# USB.net
KiCad netlist of a schematic drawn in Altium Designer
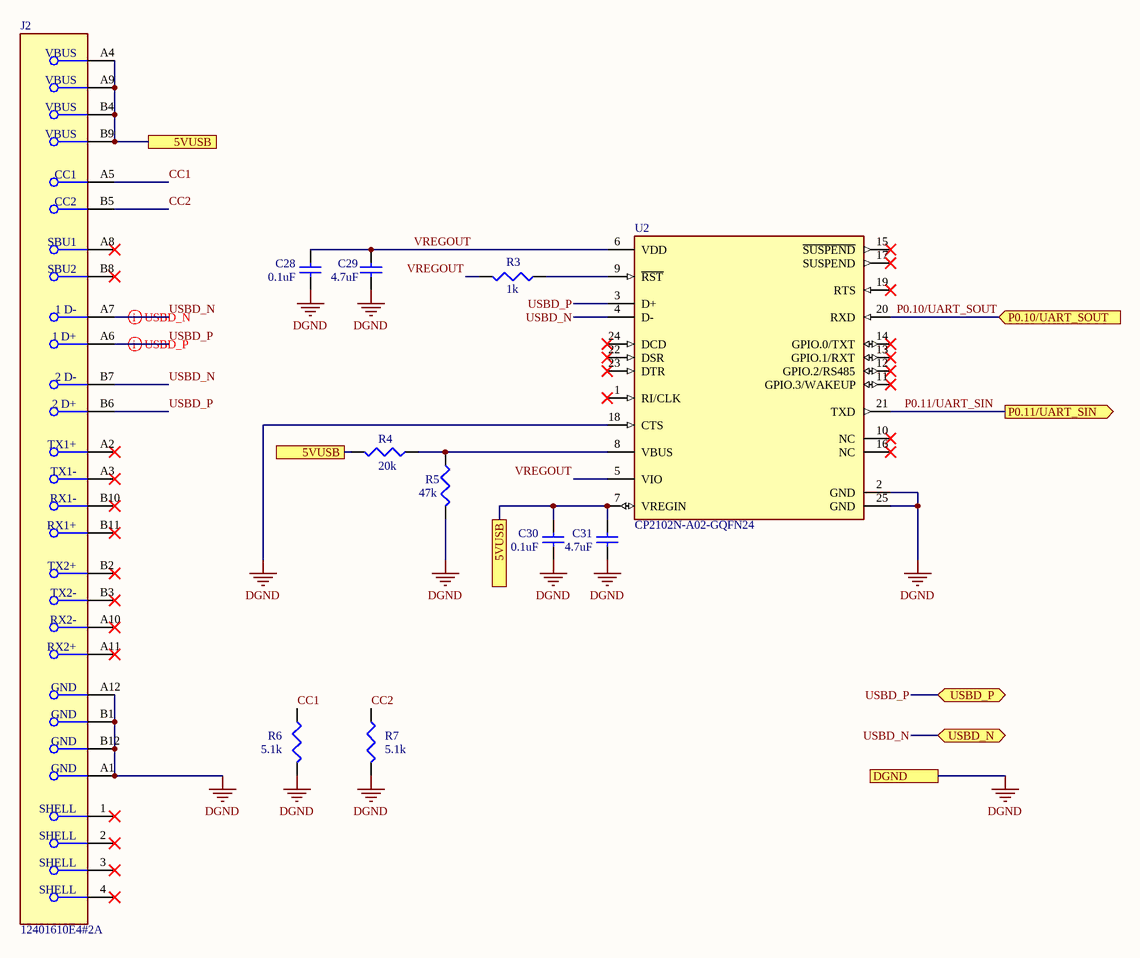
[diagram p0: USB.SchDoc]

(export (version "E")
  (design (tool "Eeschema 10.0.6"))
  (components
    (comp (ref "C28")
      (value "0.1uF")
      (footprint "0402 SMD")
      (description "0.1 µF ±10% 16V Ceramic Capacitor X7R 0402 (1005 Metric) Kemet")
      (fields (field (name "Comment") "C0402C104K4RAC7867"))
      (libsource (lib "ACEstat") (part "C0402C104K4RAC7867"))
    )
    (comp (ref "C29")
      (value "4.7uF")
      (footprint "0402 SMD")
      (description "4.7 µF ±10% 6.3V Ceramic Capacitor X5R 0402 (1005 Metric) Samsung")
      (fields (field (name "Comment") "CL05A475KQ5NRNC"))
      (libsource (lib "ACEstat") (part "CL05A475KQ5NRNC"))
    )
    (comp (ref "C30")
      (value "0.1uF")
      (footprint "0402 SMD")
      (description "0.1 µF ±10% 16V Ceramic Capacitor X7R 0402 (1005 Metric) Kemet")
      (fields (field (name "Comment") "C0402C104K4RAC7867"))
      (libsource (lib "ACEstat") (part "C0402C104K4RAC7867"))
    )
    (comp (ref "C31")
      (value "4.7uF")
      (footprint "0402 SMD")
      (description "4.7 µF ±10% 6.3V Ceramic Capacitor X5R 0402 (1005 Metric) Samsung")
      (fields (field (name "Comment") "CL05A475KQ5NRNC"))
      (libsource (lib "ACEstat") (part "CL05A475KQ5NRNC"))
    )
    (comp (ref "J2")
      (value "12401610E4#2A")
      (footprint "FP-12401610E4#2A-MFG")
      (description "CONN RCP USB3.1 TYPEC 24P SMD RA")
      (libsource (lib "Altium Content Vault") (part "7c76f4c47d7e2af8b8797da79635f2a"))
    )
    (comp (ref "R3")
      (value "1k")
      (footprint "0402 SMD")
      (description "1 kOhms ±1% 0.063W, 1/16W Chip Resistor 0402 (1005 Metric) Moisture Resistant Thick Film")
      (fields (field (name "Comment") "RC0402FR-071KL"))
      (libsource (lib "ACEstat") (part "RC0402FR-071KL"))
    )
    (comp (ref "R4")
      (value "20k")
      (footprint "0402 SMD")
      (description "20 kOhms ±1% 0.063W, 1/16W Chip Resistor 0402 (1005 Metric) Moisture Resistant Thick Film")
      (fields (field (name "Comment") "RC0402FR-0720KL"))
      (libsource (lib "ACEstat") (part "RC0402FR-0720KL"))
    )
    (comp (ref "R5")
      (value "47k")
      (footprint "0402 SMD")
      (description "47 kOhms ±1% 0.063W, 1/16W Chip Resistor 0402 (1005 Metric) Moisture Resistant Thick Film")
      (fields (field (name "Comment") "RC0402FR-0747KL"))
      (libsource (lib "ACEstat") (part "RC0402FR-0747KL"))
    )
    (comp (ref "R6")
      (value "5.1k")
      (footprint "0402 SMD")
      (description "5.1 kOhms ±1% 0.063W, 1/16W Chip Resistor 0402 (1005 Metric) Moisture Resistant Thick Film")
      (fields (field (name "Comment") "RC0402FR-075K1L"))
      (libsource (lib "ACEstat") (part "RC0402FR-075K1L"))
    )
    (comp (ref "R7")
      (value "5.1k")
      (footprint "0402 SMD")
      (description "5.1 kOhms ±1% 0.063W, 1/16W Chip Resistor 0402 (1005 Metric) Moisture Resistant Thick Film")
      (fields (field (name "Comment") "RC0402FR-075K1L"))
      (libsource (lib "ACEstat") (part "RC0402FR-075K1L"))
    )
    (comp (ref "U2")
      (value "CP2102N-A02-GQFN24")
      (footprint "FP-CP2102N-A02-GQFN24R-IPC_A")
      (description "IC USB TO UART BRIDGE QFN24")
      (libsource (lib "ACEstat") (part "CP2102N"))
    )
  )
  (nets
    (net (code "1") (name "/5VUSB") (class "Default")
      (node (ref "C30") (pin "2") (pinfunction "2_2") (pintype "passive"))
      (node (ref "C31") (pin "2") (pinfunction "2_2") (pintype "passive"))
      (node (ref "J2") (pin "A4") (pinfunction "VBUS_A4") (pintype "power_in"))
      (node (ref "J2") (pin "A9") (pinfunction "VBUS_A9") (pintype "power_in"))
      (node (ref "J2") (pin "B4") (pinfunction "VBUS_B4") (pintype "power_in"))
      (node (ref "J2") (pin "B9") (pinfunction "VBUS_B9") (pintype "power_in"))
      (node (ref "R4") (pin "2") (pinfunction "2_2") (pintype "passive"))
      (node (ref "U2") (pin "7") (pinfunction "VREGIN_7") (pintype "bidirectional"))
    )
    (net (code "2") (name "/CC1") (class "Default")
      (node (ref "J2") (pin "A5") (pinfunction "CC1_A5") (pintype "passive"))
      (node (ref "R6") (pin "1") (pinfunction "1_1") (pintype "passive"))
    )
    (net (code "3") (name "/CC2") (class "Default")
      (node (ref "J2") (pin "B5") (pinfunction "CC2_B5") (pintype "passive"))
      (node (ref "R7") (pin "1") (pinfunction "1_1") (pintype "passive"))
    )
    (net (code "4") (name "/P0.10{slash}UART_SOUT") (class "Default")
      (node (ref "U2") (pin "20") (pinfunction "RXD_20") (pintype "input"))
    )
    (net (code "5") (name "/P0.11{slash}UART_SIN") (class "Default")
      (node (ref "U2") (pin "21") (pinfunction "TXD_21") (pintype "output"))
    )
    (net (code "6") (name "/USBD_N") (class "Default")
      (node (ref "J2") (pin "A7") (pinfunction "1_D-_A7") (pintype "passive"))
      (node (ref "J2") (pin "B7") (pinfunction "2_D-_B7") (pintype "passive"))
      (node (ref "U2") (pin "4") (pinfunction "D-_4") (pintype "passive"))
    )
    (net (code "7") (name "/USBD_P") (class "Default")
      (node (ref "J2") (pin "A6") (pinfunction "1_D+_A6") (pintype "passive"))
      (node (ref "J2") (pin "B6") (pinfunction "2_D+_B6") (pintype "passive"))
      (node (ref "U2") (pin "3") (pinfunction "D+_3") (pintype "passive"))
    )
    (net (code "8") (name "/VREGOUT") (class "Default")
      (node (ref "C28") (pin "2") (pinfunction "2_2") (pintype "passive"))
      (node (ref "C29") (pin "2") (pinfunction "2_2") (pintype "passive"))
      (node (ref "R3") (pin "2") (pinfunction "2_2") (pintype "passive"))
      (node (ref "U2") (pin "5") (pinfunction "VIO_5") (pintype "power_in"))
      (node (ref "U2") (pin "6") (pinfunction "VDD_6") (pintype "power_in"))
    )
    (net (code "9") (name "DGND") (class "Default")
      (node (ref "C28") (pin "1") (pinfunction "1_1") (pintype "passive"))
      (node (ref "C29") (pin "1") (pinfunction "1_1") (pintype "passive"))
      (node (ref "C30") (pin "1") (pinfunction "1_1") (pintype "passive"))
      (node (ref "C31") (pin "1") (pinfunction "1_1") (pintype "passive"))
      (node (ref "J2") (pin "A1") (pinfunction "GND_A1") (pintype "power_in"))
      (node (ref "J2") (pin "A12") (pinfunction "GND_A12") (pintype "power_in"))
      (node (ref "J2") (pin "B1") (pinfunction "GND_B1") (pintype "power_in"))
      (node (ref "J2") (pin "B12") (pinfunction "GND_B12") (pintype "power_in"))
      (node (ref "R5") (pin "2") (pinfunction "2_2") (pintype "passive"))
      (node (ref "R6") (pin "2") (pinfunction "2_2") (pintype "passive"))
      (node (ref "R7") (pin "2") (pinfunction "2_2") (pintype "passive"))
      (node (ref "U2") (pin "18") (pinfunction "CTS_18") (pintype "input"))
      (node (ref "U2") (pin "2") (pinfunction "GND_2") (pintype "power_in"))
      (node (ref "U2") (pin "25") (pinfunction "GND_25") (pintype "power_in"))
    )
    (net (code "10") (name "Net-(U2-VBUS)") (class "Default")
      (node (ref "R4") (pin "1") (pinfunction "1_1") (pintype "passive"))
      (node (ref "R5") (pin "1") (pinfunction "1_1") (pintype "passive"))
      (node (ref "U2") (pin "8") (pinfunction "VBUS_8") (pintype "power_in"))
    )
    (net (code "11") (name "Net-(U2-~{RST})") (class "Default")
      (node (ref "R3") (pin "1") (pinfunction "1_1") (pintype "passive"))
      (node (ref "U2") (pin "9") (pinfunction "~{RST}_9") (pintype "input"))
    )
    (net (code "12") (name "unconnected-(J2-RX1+-PadB11)") (class "Default")
      (node (ref "J2") (pin "B11") (pinfunction "RX1+_B11") (pintype "passive+no_connect"))
    )
    (net (code "13") (name "unconnected-(J2-RX1--PadB10)") (class "Default")
      (node (ref "J2") (pin "B10") (pinfunction "RX1-_B10") (pintype "passive+no_connect"))
    )
    (net (code "14") (name "unconnected-(J2-RX2+-PadA11)") (class "Default")
      (node (ref "J2") (pin "A11") (pinfunction "RX2+_A11") (pintype "passive+no_connect"))
    )
    (net (code "15") (name "unconnected-(J2-RX2--PadA10)") (class "Default")
      (node (ref "J2") (pin "A10") (pinfunction "RX2-_A10") (pintype "passive+no_connect"))
    )
    (net (code "16") (name "unconnected-(J2-SBU1-PadA8)") (class "Default")
      (node (ref "J2") (pin "A8") (pinfunction "SBU1_A8") (pintype "passive+no_connect"))
    )
    (net (code "17") (name "unconnected-(J2-SBU2-PadB8)") (class "Default")
      (node (ref "J2") (pin "B8") (pinfunction "SBU2_B8") (pintype "passive+no_connect"))
    )
    (net (code "18") (name "unconnected-(J2-SHELL-Pad1)") (class "Default")
      (node (ref "J2") (pin "1") (pinfunction "SHELL_1") (pintype "power_in+no_connect"))
    )
    (net (code "19") (name "unconnected-(J2-SHELL-Pad2)") (class "Default")
      (node (ref "J2") (pin "2") (pinfunction "SHELL_2") (pintype "power_in+no_connect"))
    )
    (net (code "20") (name "unconnected-(J2-SHELL-Pad3)") (class "Default")
      (node (ref "J2") (pin "3") (pinfunction "SHELL_3") (pintype "power_in+no_connect"))
    )
    (net (code "21") (name "unconnected-(J2-SHELL-Pad4)") (class "Default")
      (node (ref "J2") (pin "4") (pinfunction "SHELL_4") (pintype "power_in+no_connect"))
    )
    (net (code "22") (name "unconnected-(J2-TX1+-PadA2)") (class "Default")
      (node (ref "J2") (pin "A2") (pinfunction "TX1+_A2") (pintype "passive+no_connect"))
    )
    (net (code "23") (name "unconnected-(J2-TX1--PadA3)") (class "Default")
      (node (ref "J2") (pin "A3") (pinfunction "TX1-_A3") (pintype "passive+no_connect"))
    )
    (net (code "24") (name "unconnected-(J2-TX2+-PadB2)") (class "Default")
      (node (ref "J2") (pin "B2") (pinfunction "TX2+_B2") (pintype "passive+no_connect"))
    )
    (net (code "25") (name "unconnected-(J2-TX2--PadB3)") (class "Default")
      (node (ref "J2") (pin "B3") (pinfunction "TX2-_B3") (pintype "passive+no_connect"))
    )
    (net (code "26") (name "unconnected-(U2-DCD-Pad24)") (class "Default")
      (node (ref "U2") (pin "24") (pinfunction "DCD_24") (pintype "input+no_connect"))
    )
    (net (code "27") (name "unconnected-(U2-DSR-Pad22)") (class "Default")
      (node (ref "U2") (pin "22") (pinfunction "DSR_22") (pintype "input+no_connect"))
    )
    (net (code "28") (name "unconnected-(U2-DTR-Pad23)") (class "Default")
      (node (ref "U2") (pin "23") (pinfunction "DTR_23") (pintype "input+no_connect"))
    )
    (net (code "29") (name "unconnected-(U2-GPIO.0{slash}TXT-Pad14)") (class "Default")
      (node (ref "U2") (pin "14") (pinfunction "GPIO.0/TXT_14") (pintype "bidirectional+no_connect"))
    )
    (net (code "30") (name "unconnected-(U2-GPIO.1{slash}RXT-Pad13)") (class "Default")
      (node (ref "U2") (pin "13") (pinfunction "GPIO.1/RXT_13") (pintype "bidirectional+no_connect"))
    )
    (net (code "31") (name "unconnected-(U2-GPIO.2{slash}RS485-Pad12)") (class "Default")
      (node (ref "U2") (pin "12") (pinfunction "GPIO.2/RS485_12") (pintype "bidirectional+no_connect"))
    )
    (net (code "32") (name "unconnected-(U2-GPIO.3{slash}WAKEUP-Pad11)") (class "Default")
      (node (ref "U2") (pin "11") (pinfunction "GPIO.3/WAKEUP_11") (pintype "bidirectional+no_connect"))
    )
    (net (code "33") (name "unconnected-(U2-NC-Pad10)") (class "Default")
      (node (ref "U2") (pin "10") (pinfunction "NC_10") (pintype "passive+no_connect"))
    )
    (net (code "34") (name "unconnected-(U2-NC-Pad16)") (class "Default")
      (node (ref "U2") (pin "16") (pinfunction "NC_16") (pintype "passive+no_connect"))
    )
    (net (code "35") (name "unconnected-(U2-RI{slash}CLK-Pad1)") (class "Default")
      (node (ref "U2") (pin "1") (pinfunction "RI/CLK_1") (pintype "input+no_connect"))
    )
    (net (code "36") (name "unconnected-(U2-RTS-Pad19)") (class "Default")
      (node (ref "U2") (pin "19") (pinfunction "RTS_19") (pintype "input+no_connect"))
    )
    (net (code "37") (name "unconnected-(U2-SUSPEND-Pad17)") (class "Default")
      (node (ref "U2") (pin "17") (pinfunction "SUSPEND_17") (pintype "output+no_connect"))
    )
    (net (code "38") (name "unconnected-(U2-~{SUSPEND}-Pad15)") (class "Default")
      (node (ref "U2") (pin "15") (pinfunction "~{SUSPEND}_15") (pintype "output+no_connect"))
    )
  )
)
